# CR99004.net
KiCad netlist of a schematic drawn in Altium Designer
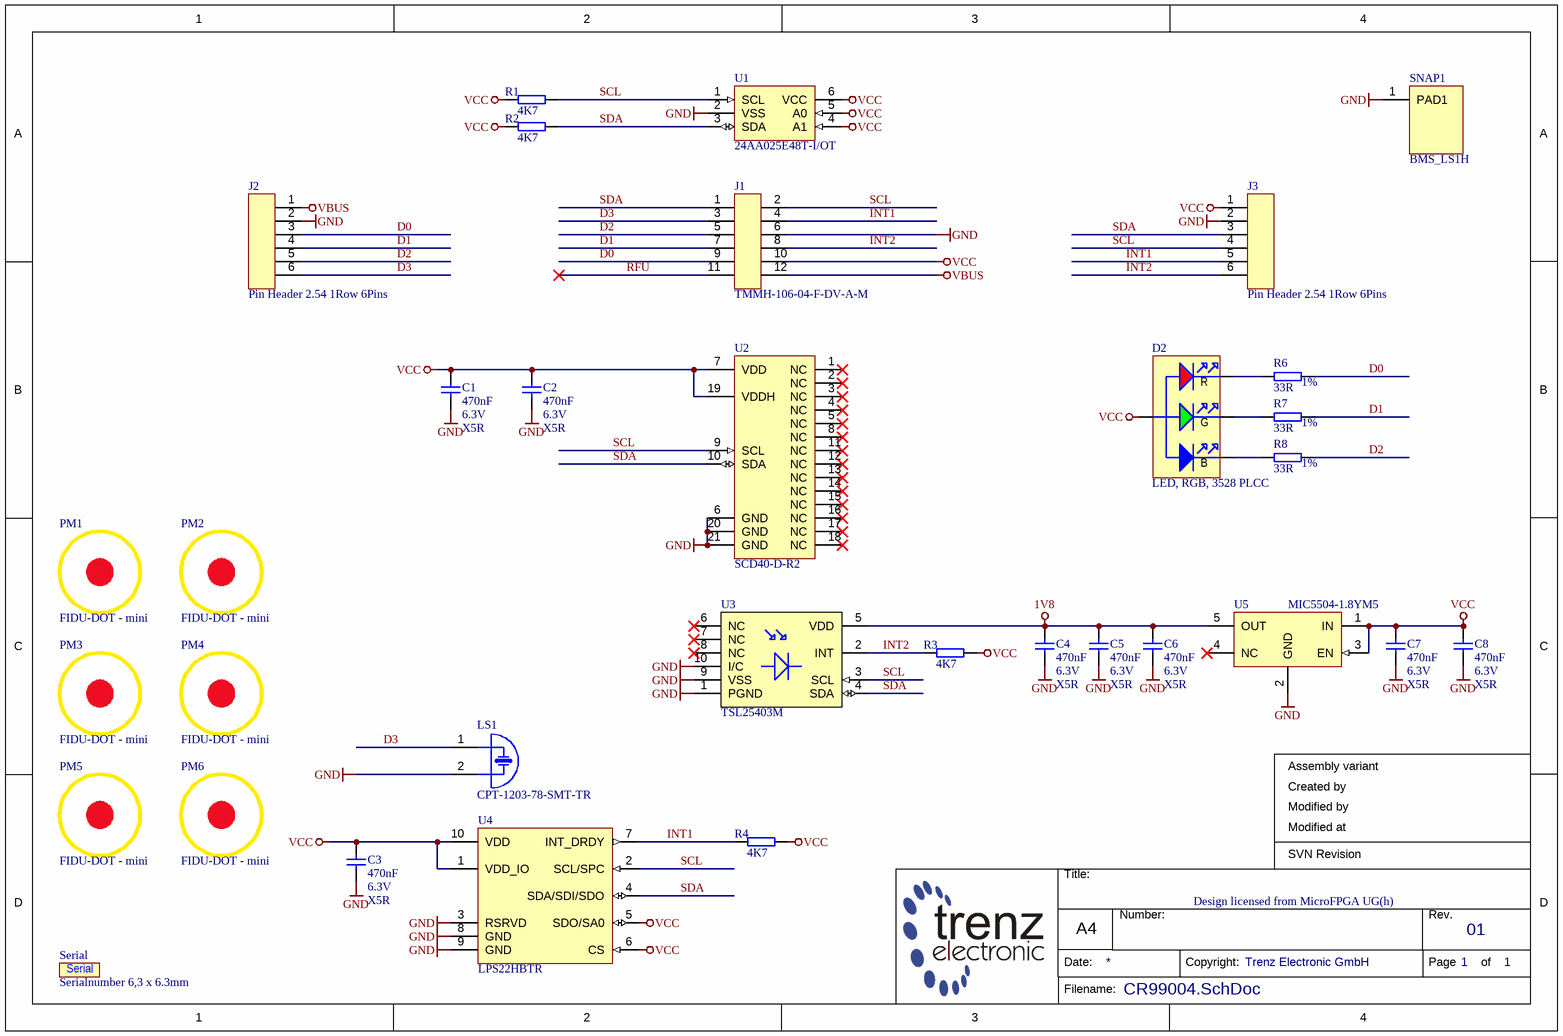
[diagram p0: CR99004.SchDoc]

(export (version "E")
  (design (tool "Eeschema 10.0.6"))
  (components
    (comp (ref "C1")
      (value "470nF")
      (footprint "CAPC0603X33N_V")
      (description "KON 470nF 6.3V X5R 20%  SMD BF 0603 (0201)")
      (fields
        (field (name "VOLTAGE") "6.3V")
        (field (name "TECHNOLOGY") "X5R")
        (field (name "TOLERANCE") "20%")
      )
      (libsource (lib "TE") (part "CAP-NP"))
    )
    (comp (ref "C2")
      (value "470nF")
      (footprint "CAPC0603X33N_V")
      (description "KON 470nF 6.3V X5R 20%  SMD BF 0603 (0201)")
      (fields
        (field (name "VOLTAGE") "6.3V")
        (field (name "TECHNOLOGY") "X5R")
        (field (name "TOLERANCE") "20%")
      )
      (libsource (lib "TE") (part "CAP-NP"))
    )
    (comp (ref "C3")
      (value "470nF")
      (footprint "CAPC0603X33N_V")
      (description "KON 470nF 6.3V X5R 20%  SMD BF 0603 (0201)")
      (fields
        (field (name "VOLTAGE") "6.3V")
        (field (name "TECHNOLOGY") "X5R")
        (field (name "TOLERANCE") "20%")
      )
      (libsource (lib "TE") (part "CAP-NP"))
    )
    (comp (ref "C4")
      (value "470nF")
      (footprint "CAPC0603X33N_V")
      (description "KON 470nF 6.3V X5R 20%  SMD BF 0603 (0201)")
      (fields
        (field (name "VOLTAGE") "6.3V")
        (field (name "TECHNOLOGY") "X5R")
        (field (name "TOLERANCE") "20%")
      )
      (libsource (lib "TE") (part "CAP-NP"))
    )
    (comp (ref "C5")
      (value "470nF")
      (footprint "CAPC0603X33N_V")
      (description "KON 470nF 6.3V X5R 20%  SMD BF 0603 (0201)")
      (fields
        (field (name "VOLTAGE") "6.3V")
        (field (name "TECHNOLOGY") "X5R")
        (field (name "TOLERANCE") "20%")
      )
      (libsource (lib "TE") (part "CAP-NP"))
    )
    (comp (ref "C6")
      (value "470nF")
      (footprint "CAPC0603X33N_V")
      (description "KON 470nF 6.3V X5R 20%  SMD BF 0603 (0201)")
      (fields
        (field (name "VOLTAGE") "6.3V")
        (field (name "TECHNOLOGY") "X5R")
        (field (name "TOLERANCE") "20%")
      )
      (libsource (lib "TE") (part "CAP-NP"))
    )
    (comp (ref "C7")
      (value "470nF")
      (footprint "CAPC0603X33N_V")
      (description "KON 470nF 6.3V X5R 20%  SMD BF 0603 (0201)")
      (fields
        (field (name "VOLTAGE") "6.3V")
        (field (name "TECHNOLOGY") "X5R")
        (field (name "TOLERANCE") "20%")
      )
      (libsource (lib "TE") (part "CAP-NP"))
    )
    (comp (ref "C8")
      (value "470nF")
      (footprint "CAPC0603X33N_V")
      (description "KON 470nF 6.3V X5R 20%  SMD BF 0603 (0201)")
      (fields
        (field (name "VOLTAGE") "6.3V")
        (field (name "TECHNOLOGY") "X5R")
        (field (name "TOLERANCE") "20%")
      )
      (libsource (lib "TE") (part "CAP-NP"))
    )
    (comp (ref "D2")
      (value "LED, RGB, 3528 PLCC")
      (footprint "PLCC150P360X280X190-4N-WE")
      (description "Chip LED RGB")
      (libsource (lib "TE") (part "150141M173100"))
    )
    (comp (ref "J1")
      (value "TMMH-106-04-F-DV-A-M")
      (footprint "TMMH-106-04-T-DV-A")
      (libsource (lib "TE") (part "CON-12"))
    )
    (comp (ref "J2")
      (value "Pin Header 2.54 1Row 6Pins")
      (footprint "STIFTLEISTE2_54 OG 1R-6")
      (description "Stiftleiste gerade 1-reihig, 6pol")
      (libsource (lib "TE") (part "CON-6"))
    )
    (comp (ref "J3")
      (value "Pin Header 2.54 1Row 6Pins")
      (footprint "STIFTLEISTE2_54 OG 1R-6")
      (description "Stiftleiste gerade 1-reihig, 6pol")
      (libsource (lib "") (part "CON-6_1"))
    )
    (comp (ref "LS1")
      (value "CPT-1203-78-SMT-TR")
      (footprint "CPT-1203-78-SMT")
      (description "Buzzers Transducer, Piezo, SMT")
      (fields (field (name "VOLTAGE") "5V"))
      (libsource (lib "TE") (part "Buzzer_Piezo"))
    )
    (comp (ref "PM1")
      (value "FIDU-DOT - mini")
      (footprint "FIDU-DOT - mini")
      (description "FIDU-DOT - MINI 0.5mm")
      (libsource (lib "TE") (part "FIDU-DOT - small"))
    )
    (comp (ref "PM2")
      (value "FIDU-DOT - mini")
      (footprint "FIDU-DOT - mini")
      (description "FIDU-DOT - MINI 0.5mm")
      (libsource (lib "TE") (part "FIDU-DOT - small"))
    )
    (comp (ref "PM3")
      (value "FIDU-DOT - mini")
      (footprint "FIDU-DOT - mini")
      (description "FIDU-DOT - MINI 0.5mm")
      (libsource (lib "TE") (part "FIDU-DOT - small"))
    )
    (comp (ref "PM4")
      (value "FIDU-DOT - mini")
      (footprint "FIDU-DOT - mini")
      (description "FIDU-DOT - MINI 0.5mm")
      (libsource (lib "TE") (part "FIDU-DOT - small"))
    )
    (comp (ref "PM5")
      (value "FIDU-DOT - mini")
      (footprint "FIDU-DOT - mini")
      (description "FIDU-DOT - MINI 0.5mm")
      (libsource (lib "TE") (part "FIDU-DOT - small"))
    )
    (comp (ref "PM6")
      (value "FIDU-DOT - mini")
      (footprint "FIDU-DOT - mini")
      (description "FIDU-DOT - MINI 0.5mm")
      (libsource (lib "TE") (part "FIDU-DOT - small"))
    )
    (comp (ref "R1")
      (value "4K7")
      (footprint "RESC1005X40N_V")
      (description "WID SMD 4K7 1% 0,063W BF 1005 (0402)")
      (fields (field (name "TOLERANCE") "1%"))
      (libsource (lib "TE") (part "RES"))
    )
    (comp (ref "R2")
      (value "4K7")
      (footprint "RESC1005X40N_V")
      (description "WID SMD 4K7 1% 0,063W BF 1005 (0402)")
      (fields (field (name "TOLERANCE") "1%"))
      (libsource (lib "TE") (part "RES"))
    )
    (comp (ref "R3")
      (value "4K7")
      (footprint "RESC1005X40N_V")
      (description "WID SMD 4K7 1% 0,063W BF 1005 (0402)")
      (fields (field (name "TOLERANCE") "1%"))
      (libsource (lib "TE") (part "RES"))
    )
    (comp (ref "R4")
      (value "4K7")
      (footprint "RESC1005X40N_V")
      (description "WID SMD 4K7 1% 0,063W BF 1005 (0402)")
      (fields (field (name "TOLERANCE") "1%"))
      (libsource (lib "TE") (part "RES"))
    )
    (comp (ref "R6")
      (value "33R")
      (footprint "RESC1005X40N_V")
      (description "WID SMD 33R 1% 0,063W BF 1005 (0402)")
      (fields (field (name "TOLERANCE") "1%"))
      (libsource (lib "TE") (part "RES"))
    )
    (comp (ref "R7")
      (value "33R")
      (footprint "RESC1005X40N_V")
      (description "WID SMD 33R 1% 0,063W BF 1005 (0402)")
      (fields (field (name "TOLERANCE") "1%"))
      (libsource (lib "TE") (part "RES"))
    )
    (comp (ref "R8")
      (value "33R")
      (footprint "RESC1005X40N_V")
      (description "WID SMD 33R 1% 0,063W BF 1005 (0402)")
      (fields (field (name "TOLERANCE") "1%"))
      (libsource (lib "TE") (part "RES"))
    )
    (comp (ref "Serial")
      (value "Serialnumber 6,3 x 6.3mm")
      (footprint "Serial_6.3x6.3mm")
      (libsource (lib "TE") (part "Serial"))
    )
    (comp (ref "SNAP1") (value "BMS_LS1H") (footprint "BMS_LS1H") (libsource (lib "BMOD") (part "BMS_LS1H")))
    (comp (ref "U1")
      (value "24AA025E48T-I/OT")
      (footprint "SOT95P280X145-6N")
      (libsource (lib "TE") (part "24AA025E48"))
    )
    (comp (ref "U2")
      (value "SCD40-D-R2")
      (footprint "PQFN125P1010X1010X680-21T480X480N")
      (libsource (lib "TE") (part "SCD40-D-R2"))
    )
    (comp (ref "U3")
      (value "TSL25403M")
      (footprint "QFN50P200X200X55-10N")
      (libsource (lib "TE") (part "TSL2540"))
    )
    (comp (ref "U4")
      (value "LPS22HBTR")
      (footprint "PQFN50P200X200X80-10N")
      (description "Pressure Sensor")
      (libsource (lib "TE") (part "LPS22HB"))
    )
    (comp (ref "U5")
      (value "MIC5504-1.8YM5")
      (footprint "SOT95P280X145-5N")
      (fields (field (name "VOLTAGE") "1.8V"))
      (libsource (lib "TE") (part "TLV70235DBV"))
    )
  )
  (nets
    (net (code "1") (name "/D0") (class "Default")
      (node (ref "J1") (pin "9") (pinfunction "9_9") (pintype "passive"))
      (node (ref "J2") (pin "3") (pintype "passive"))
      (node (ref "R6") (pin "2") (pinfunction "2_2") (pintype "passive"))
    )
    (net (code "2") (name "/D1") (class "Default")
      (node (ref "J1") (pin "7") (pinfunction "7_7") (pintype "passive"))
      (node (ref "J2") (pin "4") (pintype "passive"))
      (node (ref "R7") (pin "2") (pinfunction "2_2") (pintype "passive"))
    )
    (net (code "3") (name "/D2") (class "Default")
      (node (ref "J1") (pin "5") (pinfunction "5_5") (pintype "passive"))
      (node (ref "J2") (pin "5") (pintype "passive"))
      (node (ref "R8") (pin "2") (pinfunction "2_2") (pintype "passive"))
    )
    (net (code "4") (name "/D3") (class "Default")
      (node (ref "J1") (pin "3") (pinfunction "3_3") (pintype "passive"))
      (node (ref "J2") (pin "6") (pintype "passive"))
      (node (ref "LS1") (pin "1") (pinfunction "A_1") (pintype "passive"))
    )
    (net (code "5") (name "/INT1") (class "Default")
      (node (ref "J1") (pin "4") (pinfunction "4_4") (pintype "passive"))
      (node (ref "J3") (pin "5") (pintype "passive"))
      (node (ref "R4") (pin "1") (pinfunction "1_1") (pintype "passive"))
      (node (ref "U4") (pin "7") (pinfunction "INT_DRDY_7") (pintype "output"))
    )
    (net (code "6") (name "/INT2") (class "Default")
      (node (ref "J1") (pin "8") (pinfunction "8_8") (pintype "passive"))
      (node (ref "J3") (pin "6") (pintype "passive"))
      (node (ref "R3") (pin "1") (pinfunction "1_1") (pintype "passive"))
      (node (ref "U3") (pin "2") (pinfunction "INT_2") (pintype "open_collector"))
    )
    (net (code "7") (name "/RFU") (class "Default")
      (node (ref "J1") (pin "11") (pinfunction "11_11") (pintype "passive+no_connect"))
    )
    (net (code "8") (name "/SCL") (class "Default")
      (node (ref "J1") (pin "2") (pinfunction "2_2") (pintype "passive"))
      (node (ref "J3") (pin "4") (pintype "passive"))
      (node (ref "R1") (pin "2") (pinfunction "2_2") (pintype "passive"))
      (node (ref "U1") (pin "1") (pinfunction "SCL_1") (pintype "input"))
      (node (ref "U2") (pin "9") (pinfunction "SCL_9") (pintype "input"))
      (node (ref "U3") (pin "3") (pinfunction "SCL_3") (pintype "input"))
      (node (ref "U4") (pin "2") (pinfunction "SCL/SPC_2") (pintype "input"))
    )
    (net (code "9") (name "/SDA") (class "Default")
      (node (ref "J1") (pin "1") (pinfunction "1_1") (pintype "passive"))
      (node (ref "J3") (pin "3") (pintype "passive"))
      (node (ref "R2") (pin "2") (pinfunction "2_2") (pintype "passive"))
      (node (ref "U1") (pin "3") (pinfunction "SDA_3") (pintype "bidirectional"))
      (node (ref "U2") (pin "10") (pinfunction "SDA_10") (pintype "bidirectional"))
      (node (ref "U3") (pin "4") (pinfunction "SDA_4") (pintype "bidirectional"))
      (node (ref "U4") (pin "4") (pinfunction "SDA/SDI/SDO_4") (pintype "bidirectional"))
    )
    (net (code "10") (name "1V8") (class "Default")
      (node (ref "C4") (pin "2") (pinfunction "2_2") (pintype "passive"))
      (node (ref "C5") (pin "2") (pinfunction "2_2") (pintype "passive"))
      (node (ref "C6") (pin "2") (pinfunction "2_2") (pintype "passive"))
      (node (ref "U3") (pin "5") (pinfunction "VDD_5") (pintype "power_in"))
      (node (ref "U5") (pin "5") (pinfunction "OUT_5") (pintype "power_in"))
    )
    (net (code "11") (name "GND") (class "Default")
      (node (ref "C1") (pin "2") (pinfunction "2_2") (pintype "passive"))
      (node (ref "C2") (pin "2") (pinfunction "2_2") (pintype "passive"))
      (node (ref "C3") (pin "2") (pinfunction "2_2") (pintype "passive"))
      (node (ref "C4") (pin "1") (pinfunction "1_1") (pintype "passive"))
      (node (ref "C5") (pin "1") (pinfunction "1_1") (pintype "passive"))
      (node (ref "C6") (pin "1") (pinfunction "1_1") (pintype "passive"))
      (node (ref "C7") (pin "1") (pinfunction "1_1") (pintype "passive"))
      (node (ref "C8") (pin "1") (pinfunction "1_1") (pintype "passive"))
      (node (ref "J1") (pin "6") (pinfunction "6_6") (pintype "passive"))
      (node (ref "J2") (pin "2") (pintype "passive"))
      (node (ref "J3") (pin "2") (pintype "passive"))
      (node (ref "LS1") (pin "2") (pinfunction "K_2") (pintype "passive"))
      (node (ref "SNAP1") (pin "1") (pinfunction "PAD1_1") (pintype "power_in"))
      (node (ref "U1") (pin "2") (pinfunction "VSS_2") (pintype "power_in"))
      (node (ref "U2") (pin "20") (pinfunction "GND_20") (pintype "power_in"))
      (node (ref "U2") (pin "21") (pinfunction "GND_21") (pintype "power_in"))
      (node (ref "U2") (pin "6") (pinfunction "GND_6") (pintype "power_in"))
      (node (ref "U3") (pin "1") (pinfunction "PGND_1") (pintype "power_in"))
      (node (ref "U3") (pin "10") (pinfunction "I/C_10") (pintype "passive"))
      (node (ref "U3") (pin "9") (pinfunction "VSS_9") (pintype "power_in"))
      (node (ref "U4") (pin "3") (pinfunction "RSRVD_3") (pintype "power_in"))
      (node (ref "U4") (pin "8") (pinfunction "GND_8") (pintype "power_in"))
      (node (ref "U4") (pin "9") (pinfunction "GND_9") (pintype "power_in"))
      (node (ref "U5") (pin "2") (pinfunction "GND_2") (pintype "power_in"))
    )
    (net (code "12") (name "Net-(D2-BLUE)") (class "Default")
      (node (ref "D2") (pin "2") (pinfunction "BLUE_2") (pintype "passive"))
      (node (ref "R8") (pin "1") (pinfunction "1_1") (pintype "passive"))
    )
    (net (code "13") (name "Net-(D2-GREEN)") (class "Default")
      (node (ref "D2") (pin "4") (pinfunction "GREEN_4") (pintype "passive"))
      (node (ref "R7") (pin "1") (pinfunction "1_1") (pintype "passive"))
    )
    (net (code "14") (name "Net-(D2-RED)") (class "Default")
      (node (ref "D2") (pin "3") (pinfunction "RED_3") (pintype "passive"))
      (node (ref "R6") (pin "1") (pinfunction "1_1") (pintype "passive"))
    )
    (net (code "15") (name "VBUS") (class "Default")
      (node (ref "J1") (pin "12") (pinfunction "12_12") (pintype "passive"))
      (node (ref "J2") (pin "1") (pintype "passive"))
    )
    (net (code "16") (name "VCC") (class "Default")
      (node (ref "C1") (pin "1") (pinfunction "1_1") (pintype "passive"))
      (node (ref "C2") (pin "1") (pinfunction "1_1") (pintype "passive"))
      (node (ref "C3") (pin "1") (pinfunction "1_1") (pintype "passive"))
      (node (ref "C7") (pin "2") (pinfunction "2_2") (pintype "passive"))
      (node (ref "C8") (pin "2") (pinfunction "2_2") (pintype "passive"))
      (node (ref "D2") (pin "1") (pinfunction "ANODE_1") (pintype "passive"))
      (node (ref "J1") (pin "10") (pinfunction "10_10") (pintype "passive"))
      (node (ref "J3") (pin "1") (pintype "passive"))
      (node (ref "R1") (pin "1") (pinfunction "1_1") (pintype "passive"))
      (node (ref "R2") (pin "1") (pinfunction "1_1") (pintype "passive"))
      (node (ref "R3") (pin "2") (pinfunction "2_2") (pintype "passive"))
      (node (ref "R4") (pin "2") (pinfunction "2_2") (pintype "passive"))
      (node (ref "U1") (pin "4") (pinfunction "A1_4") (pintype "input"))
      (node (ref "U1") (pin "5") (pinfunction "A0_5") (pintype "input"))
      (node (ref "U1") (pin "6") (pinfunction "VCC_6") (pintype "power_in"))
      (node (ref "U2") (pin "19") (pinfunction "VDDH_19") (pintype "power_in"))
      (node (ref "U2") (pin "7") (pinfunction "VDD_7") (pintype "power_in"))
      (node (ref "U4") (pin "1") (pinfunction "VDD_IO_1") (pintype "power_in"))
      (node (ref "U4") (pin "10") (pinfunction "VDD_10") (pintype "power_in"))
      (node (ref "U4") (pin "5") (pinfunction "SDO/SA0_5") (pintype "bidirectional"))
      (node (ref "U4") (pin "6") (pinfunction "CS_6") (pintype "input"))
      (node (ref "U5") (pin "1") (pinfunction "IN_1") (pintype "power_in"))
      (node (ref "U5") (pin "3") (pinfunction "EN_3") (pintype "input"))
    )
    (net (code "17") (name "unconnected-(U2-NC-Pad1)") (class "Default")
      (node (ref "U2") (pin "1") (pinfunction "NC_1") (pintype "passive+no_connect"))
    )
    (net (code "18") (name "unconnected-(U2-NC-Pad2)") (class "Default")
      (node (ref "U2") (pin "2") (pinfunction "NC_2") (pintype "passive+no_connect"))
    )
    (net (code "19") (name "unconnected-(U2-NC-Pad3)") (class "Default")
      (node (ref "U2") (pin "3") (pinfunction "NC_3") (pintype "passive+no_connect"))
    )
    (net (code "20") (name "unconnected-(U2-NC-Pad4)") (class "Default")
      (node (ref "U2") (pin "4") (pinfunction "NC_4") (pintype "passive+no_connect"))
    )
    (net (code "21") (name "unconnected-(U2-NC-Pad5)") (class "Default")
      (node (ref "U2") (pin "5") (pinfunction "NC_5") (pintype "passive+no_connect"))
    )
    (net (code "22") (name "unconnected-(U2-NC-Pad8)") (class "Default")
      (node (ref "U2") (pin "8") (pinfunction "NC_8") (pintype "passive+no_connect"))
    )
    (net (code "23") (name "unconnected-(U2-NC-Pad11)") (class "Default")
      (node (ref "U2") (pin "11") (pinfunction "NC_11") (pintype "passive+no_connect"))
    )
    (net (code "24") (name "unconnected-(U2-NC-Pad12)") (class "Default")
      (node (ref "U2") (pin "12") (pinfunction "NC_12") (pintype "passive+no_connect"))
    )
    (net (code "25") (name "unconnected-(U2-NC-Pad13)") (class "Default")
      (node (ref "U2") (pin "13") (pinfunction "NC_13") (pintype "passive+no_connect"))
    )
    (net (code "26") (name "unconnected-(U2-NC-Pad14)") (class "Default")
      (node (ref "U2") (pin "14") (pinfunction "NC_14") (pintype "passive+no_connect"))
    )
    (net (code "27") (name "unconnected-(U2-NC-Pad15)") (class "Default")
      (node (ref "U2") (pin "15") (pinfunction "NC_15") (pintype "passive+no_connect"))
    )
    (net (code "28") (name "unconnected-(U2-NC-Pad16)") (class "Default")
      (node (ref "U2") (pin "16") (pinfunction "NC_16") (pintype "passive+no_connect"))
    )
    (net (code "29") (name "unconnected-(U2-NC-Pad17)") (class "Default")
      (node (ref "U2") (pin "17") (pinfunction "NC_17") (pintype "passive+no_connect"))
    )
    (net (code "30") (name "unconnected-(U2-NC-Pad18)") (class "Default")
      (node (ref "U2") (pin "18") (pinfunction "NC_18") (pintype "passive+no_connect"))
    )
    (net (code "31") (name "unconnected-(U3-NC-Pad6)") (class "Default")
      (node (ref "U3") (pin "6") (pinfunction "NC_6") (pintype "passive+no_connect"))
    )
    (net (code "32") (name "unconnected-(U3-NC-Pad7)") (class "Default")
      (node (ref "U3") (pin "7") (pinfunction "NC_7") (pintype "passive+no_connect"))
    )
    (net (code "33") (name "unconnected-(U3-NC-Pad8)") (class "Default")
      (node (ref "U3") (pin "8") (pinfunction "NC_8") (pintype "passive+no_connect"))
    )
    (net (code "34") (name "unconnected-(U5-NC-Pad4)") (class "Default")
      (node (ref "U5") (pin "4") (pinfunction "NC_4") (pintype "passive+no_connect"))
    )
  )
)
